# AVRISP2TC.net
KiCad netlist of a schematic drawn in EAGLE
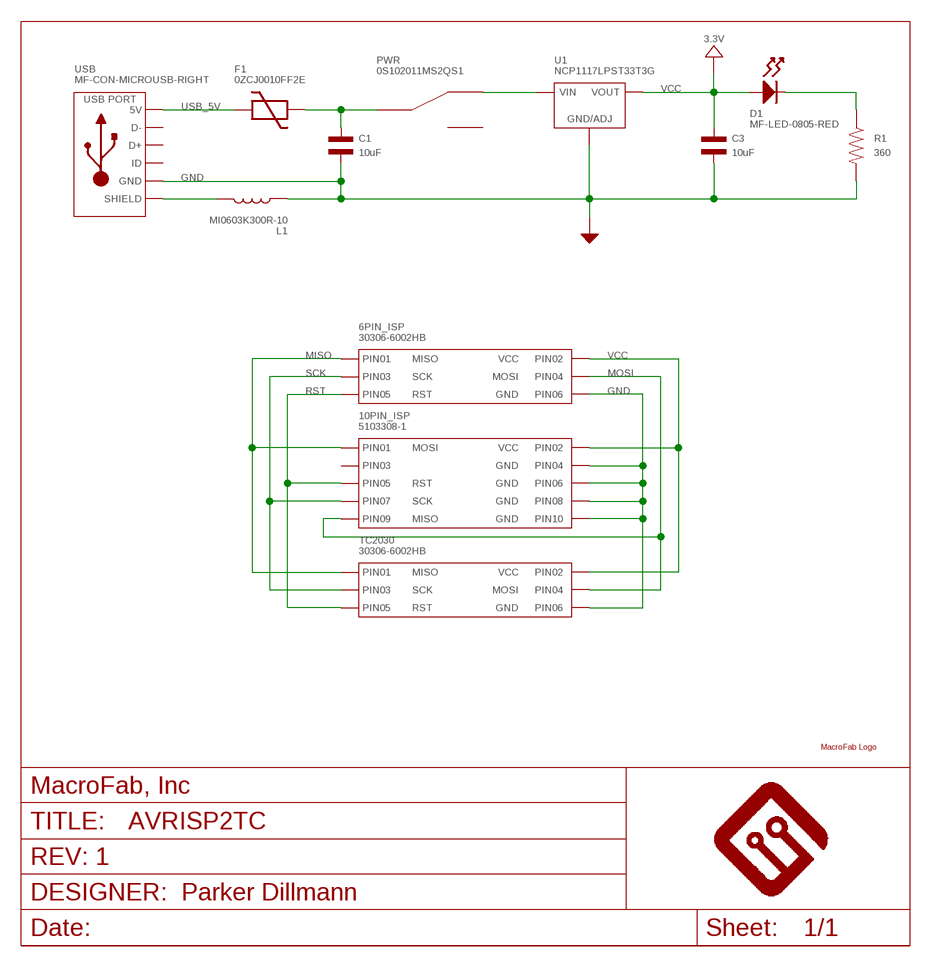
[diagram p0: schematic, sheet 1]

(export (version "E")
  (design (tool "Eeschema 10.0.6"))
  (components
    (comp (ref "6PIN_ISP")
      (value "30306-6002HB")
      (footprint "eagle-import:30306-6002HB")
      (fields
        (field (name "LABEL01") "MISO")
        (field (name "LABEL02") "VCC")
        (field (name "LABEL03") "SCK")
        (field (name "LABEL04") "MOSI")
        (field (name "LABEL05") "RST")
        (field (name "LABEL06") "GND")
      )
      (libsource (lib "eagle-import") (part "CON_02X03_30306-6002HB"))
    )
    (comp (ref "10PIN_ISP")
      (value "5103308-1")
      (footprint "eagle-import:5103308-1")
      (fields
        (field (name "LABEL01") "MOSI")
        (field (name "LABEL02") "VCC")
        (field (name "LABEL04") "GND")
        (field (name "LABEL05") "RST")
        (field (name "LABEL06") "GND")
        (field (name "LABEL07") "SCK")
        (field (name "LABEL08") "GND")
        (field (name "LABEL09") "MISO")
        (field (name "LABEL10") "GND")
      )
      (libsource (lib "eagle-import") (part "CON_02X05_5103308-1"))
    )
    (comp (ref "C1")
      (value "10uF")
      (footprint "eagle-import:C1206")
      (fields (field (name "MPN") "MF-CAP-1206-10uF"))
      (libsource (lib "eagle-import") (part "CAPACITOR_NP_1206"))
    )
    (comp (ref "C3")
      (value "10uF")
      (footprint "eagle-import:C1206")
      (fields (field (name "MPN") "MF-CAP-1206-10uF"))
      (libsource (lib "eagle-import") (part "CAPACITOR_NP_1206"))
    )
    (comp (ref "D1")
      (value "MF-LED-0805-RED")
      (footprint "eagle-import:LED0805")
      (fields (field (name "HOUSEPART") "YES"))
      (libsource (lib "eagle-import") (part "LED_SINGLE-0805-RED"))
    )
    (comp (ref "F1")
      (value "0ZCJ0010FF2E")
      (footprint "eagle-import:1206")
      (libsource (lib "eagle-import") (part "PTC_FUSE_1206"))
    )
    (comp (ref "FRAME1")
      (value "MF_FRAMEDEFAULT")
      (footprint "eagle-import:MF_FRAME_DEFAULT")
      (fields
        (field (name "HOUSEPART") "0")
        (field (name "DNAME") "Parker Dillmann")
        (field (name "REVNUM") "REV: 1")
      )
      (libsource (lib "eagle-import") (part "MF_FRAMEDEFAULT"))
    )
    (comp (ref "L1")
      (value "MI0603K300R-10")
      (footprint "eagle-import:L0603")
      (fields (field (name "MPN") "MI0603K300R-10"))
      (libsource (lib "eagle-import") (part "INDUCTOR_0603"))
    )
    (comp (ref "PWR")
      (value "0S102011MS2QS1")
      (footprint "eagle-import:0S102011MS2QS1")
      (libsource (lib "eagle-import") (part "SPDT_0S102011MS2QS1"))
    )
    (comp (ref "R1")
      (value "360")
      (footprint "eagle-import:R0805")
      (fields (field (name "MPN") "MF-RES-0805-360"))
      (libsource (lib "eagle-import") (part "RESISTOR_0805"))
    )
    (comp (ref "TC2030")
      (value "30306-6002HB")
      (footprint "eagle-import:30306-6002HB")
      (fields
        (field (name "LABEL01") "MISO")
        (field (name "LABEL02") "VCC")
        (field (name "LABEL03") "SCK")
        (field (name "LABEL04") "MOSI")
        (field (name "LABEL05") "RST")
        (field (name "LABEL06") "GND")
      )
      (libsource (lib "eagle-import") (part "CON_02X03_30306-6002HB"))
    )
    (comp (ref "U$3")
      (value "MF_LOGOLOGO_MEDIUM")
      (footprint "eagle-import:MF_LOGO_MEDIUM")
      (libsource (lib "eagle-import") (part "MF_LOGOLOGO_MEDIUM"))
    )
    (comp (ref "U1")
      (value "NCP1117LPST33T3G")
      (footprint "eagle-import:SOT-223-3")
      (fields (field (name "HOUSEPART") "NO"))
      (libsource (lib "eagle-import") (part "NCP1117LPST33T3G"))
    )
    (comp (ref "USB")
      (value "MF-CON-MICROUSB-RIGHT")
      (footprint "eagle-import:MICROUSB-RIGHT")
      (fields (field (name "HOUSEPART") "YES"))
      (libsource (lib "eagle-import") (part "USB_MICRO_RIGHT"))
    )
  )
  (nets
    (net (code "1") (name "/MISO") (class "Default")
      (node (ref "10PIN_ISP") (pin "1") (pinfunction "PIN1_1") (pintype "bidirectional"))
      (node (ref "6PIN_ISP") (pin "1") (pinfunction "PIN1_1") (pintype "bidirectional"))
      (node (ref "TC2030") (pin "1") (pinfunction "PIN1_1") (pintype "bidirectional"))
    )
    (net (code "2") (name "/MOSI") (class "Default")
      (node (ref "10PIN_ISP") (pin "9") (pinfunction "PIN9_9") (pintype "bidirectional"))
      (node (ref "6PIN_ISP") (pin "4") (pinfunction "PIN4_4") (pintype "bidirectional"))
      (node (ref "TC2030") (pin "4") (pinfunction "PIN4_4") (pintype "bidirectional"))
    )
    (net (code "3") (name "/RST") (class "Default")
      (node (ref "10PIN_ISP") (pin "5") (pinfunction "PIN5_5") (pintype "bidirectional"))
      (node (ref "6PIN_ISP") (pin "5") (pinfunction "PIN5_5") (pintype "bidirectional"))
      (node (ref "TC2030") (pin "5") (pinfunction "PIN5_5") (pintype "bidirectional"))
    )
    (net (code "4") (name "/SCK") (class "Default")
      (node (ref "10PIN_ISP") (pin "7") (pinfunction "PIN7_7") (pintype "bidirectional"))
      (node (ref "6PIN_ISP") (pin "3") (pinfunction "PIN3_3") (pintype "bidirectional"))
      (node (ref "TC2030") (pin "3") (pinfunction "PIN3_3") (pintype "bidirectional"))
    )
    (net (code "5") (name "/USB_5V") (class "Default")
      (node (ref "F1") (pin "1") (pinfunction "P$1_1") (pintype "bidirectional"))
      (node (ref "USB") (pin "1") (pinfunction "5V_1") (pintype "power_in"))
    )
    (net (code "6") (name "3.3V") (class "Default")
      (node (ref "10PIN_ISP") (pin "2") (pinfunction "PIN2_2") (pintype "bidirectional"))
      (node (ref "6PIN_ISP") (pin "2") (pinfunction "PIN2_2") (pintype "bidirectional"))
      (node (ref "C3") (pin "P$1") (pinfunction "P$1_P$1") (pintype "passive"))
      (node (ref "D1") (pin "ANODE") (pinfunction "ANODE_ANODE") (pintype "power_in"))
      (node (ref "TC2030") (pin "2") (pinfunction "PIN2_2") (pintype "bidirectional"))
      (node (ref "U1") (pin "P$1") (pinfunction "VOUT_P$1") (pintype "bidirectional"))
      (node (ref "U1") (pin "P$3") (pinfunction "VOUT_P$3") (pintype "bidirectional"))
    )
    (net (code "7") (name "GND_RAIL") (class "Default")
      (node (ref "10PIN_ISP") (pin "10") (pinfunction "PIN10_10") (pintype "bidirectional"))
      (node (ref "10PIN_ISP") (pin "4") (pinfunction "PIN4_4") (pintype "bidirectional"))
      (node (ref "10PIN_ISP") (pin "6") (pinfunction "PIN6_6") (pintype "bidirectional"))
      (node (ref "10PIN_ISP") (pin "8") (pinfunction "PIN8_8") (pintype "bidirectional"))
      (node (ref "6PIN_ISP") (pin "6") (pinfunction "PIN6_6") (pintype "bidirectional"))
      (node (ref "C1") (pin "P$2") (pinfunction "P$2_P$2") (pintype "passive"))
      (node (ref "C3") (pin "P$2") (pinfunction "P$2_P$2") (pintype "passive"))
      (node (ref "L1") (pin "P$1") (pinfunction "P$1_P$1") (pintype "passive"))
      (node (ref "R1") (pin "P$2") (pinfunction "P$2_P$2") (pintype "passive"))
      (node (ref "TC2030") (pin "6") (pinfunction "PIN6_6") (pintype "bidirectional"))
      (node (ref "U1") (pin "P$2") (pinfunction "GND/ADJ_P$2") (pintype "bidirectional"))
      (node (ref "USB") (pin "5") (pinfunction "GND_5") (pintype "power_in"))
    )
    (net (code "8") (name "Net-(D1-PadCATHODE)") (class "Default")
      (node (ref "D1") (pin "CATHODE") (pinfunction "CATHODE_CATHODE") (pintype "power_in"))
      (node (ref "R1") (pin "P$1") (pinfunction "P$1_P$1") (pintype "passive"))
    )
    (net (code "9") (name "Net-(F1-P$2)") (class "Default")
      (node (ref "C1") (pin "P$1") (pinfunction "P$1_P$1") (pintype "passive"))
      (node (ref "F1") (pin "2") (pinfunction "P$2_2") (pintype "bidirectional"))
      (node (ref "PWR") (pin "2") (pinfunction "C_2") (pintype "bidirectional"))
    )
    (net (code "10") (name "Net-(L1-PadP$2)") (class "Default")
      (node (ref "L1") (pin "P$2") (pinfunction "P$2_P$2") (pintype "passive"))
      (node (ref "USB") (pin "S1") (pinfunction "SLD_S1") (pintype "power_in"))
      (node (ref "USB") (pin "S2") (pinfunction "SLD_S2") (pintype "power_in"))
      (node (ref "USB") (pin "S3") (pinfunction "SLD_S3") (pintype "power_in"))
      (node (ref "USB") (pin "S4") (pinfunction "SLD_S4") (pintype "power_in"))
      (node (ref "USB") (pin "S5") (pinfunction "SLD_S5") (pintype "power_in"))
      (node (ref "USB") (pin "S6") (pinfunction "SLD_S6") (pintype "power_in"))
    )
    (net (code "11") (name "Net-(U1-VIN)") (class "Default")
      (node (ref "PWR") (pin "1") (pinfunction "1_1") (pintype "bidirectional"))
      (node (ref "U1") (pin "P$4") (pinfunction "VIN_P$4") (pintype "bidirectional"))
    )
    (net (code "12") (name "unconnected-(10PIN_ISP-PIN3-Pad3)") (class "Default")
      (node (ref "10PIN_ISP") (pin "3") (pinfunction "PIN3_3") (pintype "bidirectional"))
    )
    (net (code "13") (name "unconnected-(PWR-2-Pad3)") (class "Default")
      (node (ref "PWR") (pin "3") (pinfunction "2_3") (pintype "bidirectional"))
    )
    (net (code "14") (name "unconnected-(USB-D+-Pad3)") (class "Default")
      (node (ref "USB") (pin "3") (pinfunction "D+_3") (pintype "bidirectional"))
    )
    (net (code "15") (name "unconnected-(USB-D--Pad2)") (class "Default")
      (node (ref "USB") (pin "2") (pinfunction "D-_2") (pintype "bidirectional"))
    )
    (net (code "16") (name "unconnected-(USB-ID-Pad4)") (class "Default")
      (node (ref "USB") (pin "4") (pinfunction "ID_4") (pintype "bidirectional"))
    )
  )
)
